# 5d.net
KiCad netlist of a schematic drawn in EAGLE
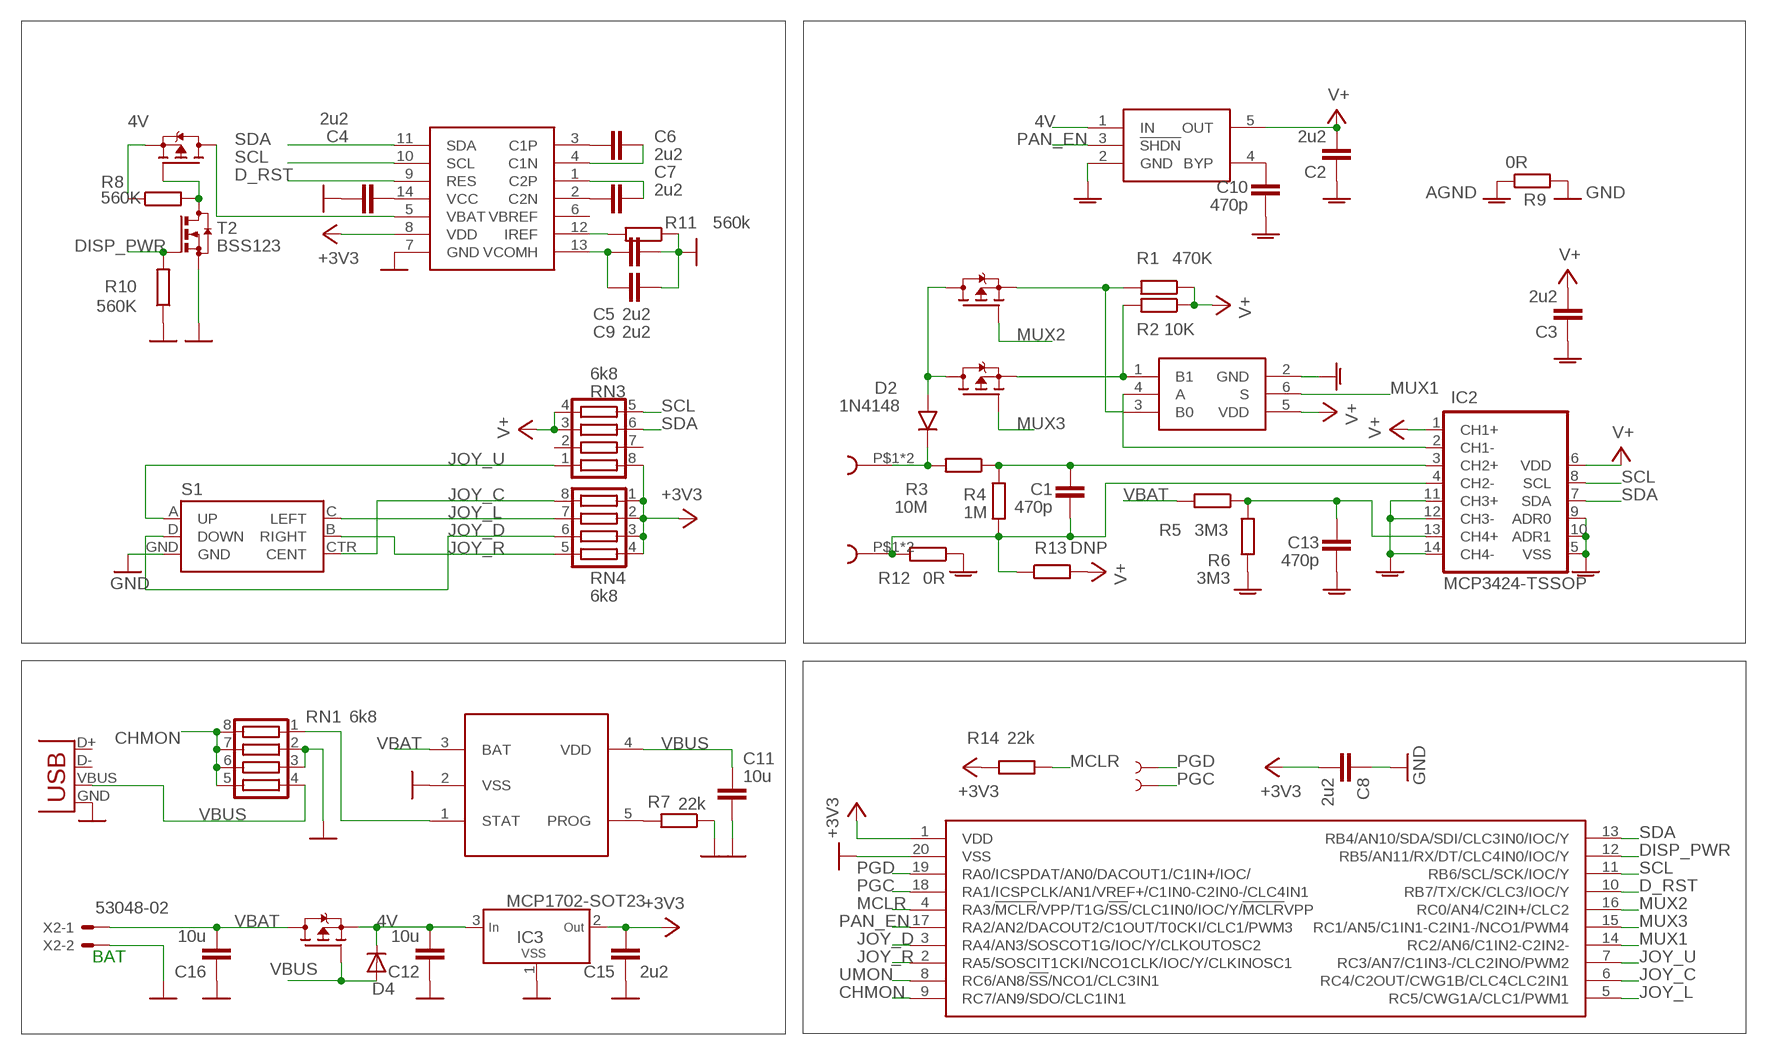
[diagram p0: schematic, sheet 1]

(export (version "E")
  (design (tool "Eeschema 10.0.6"))
  (components
    (comp (ref "C1")
      (value "470p")
      (footprint "eagle-import:0603")
      (libsource (lib "eagle-import") (part "C_0603"))
    )
    (comp (ref "C2")
      (value "2u2")
      (footprint "eagle-import:0603")
      (libsource (lib "eagle-import") (part "C_0603"))
    )
    (comp (ref "C3")
      (value "2u2")
      (footprint "eagle-import:0603")
      (libsource (lib "eagle-import") (part "C_0603"))
    )
    (comp (ref "C4")
      (value "2u2")
      (footprint "eagle-import:0603")
      (libsource (lib "eagle-import") (part "C_0603"))
    )
    (comp (ref "C5")
      (value "2u2")
      (footprint "eagle-import:0603")
      (libsource (lib "eagle-import") (part "C_0603"))
    )
    (comp (ref "C6")
      (value "2u2")
      (footprint "eagle-import:0603")
      (libsource (lib "eagle-import") (part "C_0603"))
    )
    (comp (ref "C7")
      (value "2u2")
      (footprint "eagle-import:0603")
      (libsource (lib "eagle-import") (part "C_0603"))
    )
    (comp (ref "C8")
      (value "2u2")
      (footprint "eagle-import:0603")
      (libsource (lib "eagle-import") (part "C_0603"))
    )
    (comp (ref "C9")
      (value "2u2")
      (footprint "eagle-import:0603")
      (libsource (lib "eagle-import") (part "C_0603"))
    )
    (comp (ref "C10")
      (value "470p")
      (footprint "eagle-import:0603")
      (libsource (lib "eagle-import") (part "C_0603"))
    )
    (comp (ref "C11")
      (value "10u")
      (footprint "eagle-import:R0805")
      (libsource (lib "eagle-import") (part "C_0806"))
    )
    (comp (ref "C12")
      (value "10u")
      (footprint "eagle-import:R0805")
      (libsource (lib "eagle-import") (part "C_0806"))
    )
    (comp (ref "C13")
      (value "470p")
      (footprint "eagle-import:0603")
      (libsource (lib "eagle-import") (part "C_0603"))
    )
    (comp (ref "C15")
      (value "2u2")
      (footprint "eagle-import:0603")
      (libsource (lib "eagle-import") (part "C_0603"))
    )
    (comp (ref "C16")
      (value "10u")
      (footprint "eagle-import:R0805")
      (libsource (lib "eagle-import") (part "C_0806"))
    )
    (comp (ref "D1")
      (value "DISP_OLED_049B")
      (footprint "eagle-import:DISP_OLED_049_B")
      (libsource (lib "eagle-import") (part "DISP_OLED_049B"))
    )
    (comp (ref "D2")
      (value "1N4148")
      (footprint "eagle-import:SOD-80")
      (libsource (lib "eagle-import") (part "1N4148SOD"))
    )
    (comp (ref "D4")
      (value "DIODE-SOD123")
      (footprint "eagle-import:SOD123")
      (libsource (lib "eagle-import") (part "DIODE-SOD123"))
    )
    (comp (ref "IC2")
      (value "MCP3424-TSSOP")
      (footprint "eagle-import:TSSOP14")
      (libsource (lib "eagle-import") (part "MCP3424-TSSOP"))
    )
    (comp (ref "IC3")
      (value "MCP1702-SOT23")
      (footprint "eagle-import:SOT23")
      (libsource (lib "eagle-import") (part "MCP1702-SOT23"))
    )
    (comp (ref "IC5")
      (value "NC7SB3157")
      (footprint "eagle-import:SC70-6")
      (libsource (lib "eagle-import") (part "NC7SB3157"))
    )
    (comp (ref "R1")
      (value "470K")
      (footprint "eagle-import:R0805")
      (libsource (lib "eagle-import") (part "R_0805"))
    )
    (comp (ref "R2")
      (value "10K")
      (footprint "eagle-import:R0805")
      (libsource (lib "eagle-import") (part "R_0805"))
    )
    (comp (ref "R3")
      (value "10M")
      (footprint "eagle-import:R0805")
      (libsource (lib "eagle-import") (part "R_0805"))
    )
    (comp (ref "R4")
      (value "1M")
      (footprint "eagle-import:R0805")
      (libsource (lib "eagle-import") (part "R_0805"))
    )
    (comp (ref "R5")
      (value "3M3")
      (footprint "eagle-import:0603")
      (libsource (lib "eagle-import") (part "R_0603"))
    )
    (comp (ref "R6")
      (value "3M3")
      (footprint "eagle-import:0603")
      (libsource (lib "eagle-import") (part "R_0603"))
    )
    (comp (ref "R7")
      (value "22k")
      (footprint "eagle-import:0603")
      (libsource (lib "eagle-import") (part "R_0603"))
    )
    (comp (ref "R8")
      (value "560K")
      (footprint "eagle-import:0603")
      (libsource (lib "eagle-import") (part "R_0603"))
    )
    (comp (ref "R9")
      (value "0R")
      (footprint "eagle-import:0603")
      (libsource (lib "eagle-import") (part "R_0603"))
    )
    (comp (ref "R10")
      (value "560K")
      (footprint "eagle-import:0603")
      (libsource (lib "eagle-import") (part "R_0603"))
    )
    (comp (ref "R11")
      (value "560k")
      (footprint "eagle-import:0603")
      (libsource (lib "eagle-import") (part "R_0603"))
    )
    (comp (ref "R12")
      (value "0R")
      (footprint "eagle-import:0603")
      (libsource (lib "eagle-import") (part "R_0603"))
    )
    (comp (ref "R13")
      (value "DNP")
      (footprint "eagle-import:0603")
      (libsource (lib "eagle-import") (part "R_0603"))
    )
    (comp (ref "R14")
      (value "22k")
      (footprint "eagle-import:0603")
      (libsource (lib "eagle-import") (part "R_0603"))
    )
    (comp (ref "RN1")
      (value "6k8")
      (footprint "eagle-import:CTS742C083")
      (libsource (lib "eagle-import") (part "CTS742C083"))
    )
    (comp (ref "RN3")
      (value "6k8")
      (footprint "eagle-import:CTS742C083")
      (libsource (lib "eagle-import") (part "CTS742C083"))
    )
    (comp (ref "RN4")
      (value "6k8")
      (footprint "eagle-import:CTS742C083")
      (libsource (lib "eagle-import") (part "CTS742C083"))
    )
    (comp (ref "S1")
      (value "JOYSTICK_MINI")
      (footprint "eagle-import:JOYSTICK_MINI")
      (libsource (lib "eagle-import") (part "JOYSTICK_MINI"))
    )
    (comp (ref "T1")
      (value "BSS84")
      (footprint "eagle-import:SOT23-3")
      (libsource (lib "eagle-import") (part "BSS84"))
    )
    (comp (ref "T2")
      (value "BSS123")
      (footprint "eagle-import:SOT23")
      (libsource (lib "eagle-import") (part "BSS123"))
    )
    (comp (ref "T3")
      (value "BSS84")
      (footprint "eagle-import:SOT23-3")
      (libsource (lib "eagle-import") (part "BSS84"))
    )
    (comp (ref "T4")
      (value "BSS84")
      (footprint "eagle-import:SOT23-3")
      (libsource (lib "eagle-import") (part "BSS84"))
    )
    (comp (ref "T5")
      (value "BSS84")
      (footprint "eagle-import:SOT23-3")
      (libsource (lib "eagle-import") (part "BSS84"))
    )
    (comp (ref "TP1")
      (value "TEST-POINT3X5")
      (footprint "eagle-import:PAD.03X.05")
      (libsource (lib "eagle-import") (part "TEST-POINT3X5"))
    )
    (comp (ref "TP2")
      (value "TEST-POINT3X5")
      (footprint "eagle-import:PAD.03X.05")
      (libsource (lib "eagle-import") (part "TEST-POINT3X5"))
    )
    (comp (ref "U$1")
      (value "BANPLUG_2")
      (footprint "eagle-import:BANPLUG_2")
      (libsource (lib "eagle-import") (part "BANPLUG_2"))
    )
    (comp (ref "U$2")
      (value "BANPLUG_2")
      (footprint "eagle-import:BANPLUG_2")
      (libsource (lib "eagle-import") (part "BANPLUG_2"))
    )
    (comp (ref "U$3")
      (value "TC1015")
      (footprint "eagle-import:SOT23-5")
      (libsource (lib "eagle-import") (part "TC1015"))
    )
    (comp (ref "U$4")
      (value "MCP73831")
      (footprint "eagle-import:SOT23-5")
      (libsource (lib "eagle-import") (part "MCP73831"))
    )
    (comp (ref "U$6")
      (value "PIC16F1508SSOP20")
      (footprint "eagle-import:SSOP20")
      (libsource (lib "eagle-import") (part "PIC16F1508SSOP20"))
    )
    (comp (ref "X1")
      (value "USB-MICROB")
      (footprint "eagle-import:USB-MICROB")
      (libsource (lib "eagle-import") (part "USB-MICROB"))
    )
    (comp (ref "X2")
      (value "53048-02")
      (footprint "eagle-import:53048-02")
      (libsource (lib "eagle-import") (part "53?-02048"))
    )
  )
  (nets
    (net (code "1") (name "+3V3") (class "Default")
      (node (ref "C15") (pin "2") (pinfunction "2_2") (pintype "passive"))
      (node (ref "C8") (pin "2") (pinfunction "2_2") (pintype "passive"))
      (node (ref "D1") (pin "8") (pinfunction "VDD_8") (pintype "bidirectional"))
      (node (ref "IC3") (pin "2") (pinfunction "OUT_2") (pintype "output"))
      (node (ref "R14") (pin "2") (pinfunction "2_2") (pintype "passive"))
      (node (ref "RN3") (pin "8") (pinfunction "8_8") (pintype "passive"))
      (node (ref "RN4") (pin "1") (pinfunction "1_1") (pintype "passive"))
      (node (ref "RN4") (pin "2") (pinfunction "2_2") (pintype "passive"))
      (node (ref "RN4") (pin "3") (pinfunction "3_3") (pintype "passive"))
      (node (ref "RN4") (pin "4") (pinfunction "4_4") (pintype "passive"))
      (node (ref "U$6") (pin "1") (pinfunction "VDD_1") (pintype "bidirectional"))
    )
    (net (code "2") (name "/4V") (class "Default")
      (node (ref "C12") (pin "2") (pinfunction "2_2") (pintype "passive"))
      (node (ref "D4") (pin "C") (pinfunction "C_C") (pintype "passive"))
      (node (ref "IC3") (pin "3") (pinfunction "IN_3") (pintype "input"))
      (node (ref "R8") (pin "1") (pinfunction "1_1") (pintype "passive"))
      (node (ref "T1") (pin "2") (pinfunction "S_2") (pintype "passive"))
      (node (ref "T3") (pin "2") (pinfunction "S_2") (pintype "passive"))
      (node (ref "U$3") (pin "1") (pinfunction "IN_1") (pintype "bidirectional"))
    )
    (net (code "3") (name "/CHMON") (class "Default")
      (node (ref "RN1") (pin "5") (pinfunction "5_5") (pintype "passive"))
      (node (ref "RN1") (pin "6") (pinfunction "6_6") (pintype "passive"))
      (node (ref "RN1") (pin "7") (pinfunction "7_7") (pintype "passive"))
      (node (ref "RN1") (pin "8") (pinfunction "8_8") (pintype "passive"))
      (node (ref "U$6") (pin "9") (pinfunction "RC7/AN9/SDO/CLC1IN1_9") (pintype "bidirectional"))
    )
    (net (code "4") (name "/DISP_PWR") (class "Default")
      (node (ref "R10") (pin "2") (pinfunction "2_2") (pintype "passive"))
      (node (ref "T2") (pin "1") (pinfunction "G_1") (pintype "passive"))
      (node (ref "U$6") (pin "12") (pinfunction "RB5/AN11/RX/DT/CLC4IN0/IOC/Y_12") (pintype "bidirectional"))
    )
    (net (code "5") (name "/D_RST") (class "Default")
      (node (ref "D1") (pin "9") (pinfunction "RES_9") (pintype "bidirectional"))
      (node (ref "U$6") (pin "10") (pinfunction "RB7/TX/CK/CLC3/IOC/Y_10") (pintype "bidirectional"))
    )
    (net (code "6") (name "/JOY_C") (class "Default")
      (node (ref "RN4") (pin "8") (pinfunction "8_8") (pintype "passive"))
      (node (ref "S1") (pin "CTR") (pinfunction "CENT_CTR") (pintype "bidirectional"))
      (node (ref "U$6") (pin "6") (pinfunction "RC4/C2OUT/CWG1B/CLC4CLC2IN1_6") (pintype "bidirectional"))
    )
    (net (code "7") (name "/JOY_D") (class "Default")
      (node (ref "RN4") (pin "6") (pinfunction "6_6") (pintype "passive"))
      (node (ref "S1") (pin "D") (pinfunction "DOWN_D") (pintype "bidirectional"))
      (node (ref "U$6") (pin "3") (pinfunction "RA4/AN3/SOSCOT1G/IOC/Y/CLKOUTOSC2_3") (pintype "bidirectional"))
    )
    (net (code "8") (name "/JOY_L") (class "Default")
      (node (ref "RN4") (pin "7") (pinfunction "7_7") (pintype "passive"))
      (node (ref "S1") (pin "C") (pinfunction "LEFT_C") (pintype "bidirectional"))
      (node (ref "U$6") (pin "5") (pinfunction "RC5/CWG1A/CLC1/PWM1_5") (pintype "bidirectional"))
    )
    (net (code "9") (name "/JOY_R") (class "Default")
      (node (ref "RN4") (pin "5") (pinfunction "5_5") (pintype "passive"))
      (node (ref "S1") (pin "B") (pinfunction "RIGHT_B") (pintype "bidirectional"))
      (node (ref "U$6") (pin "2") (pinfunction "RA5/SOSCIT1CKI/NCO1CLK/IOC/Y/CLKINOSC1_2") (pintype "bidirectional"))
    )
    (net (code "10") (name "/JOY_U") (class "Default")
      (node (ref "RN3") (pin "1") (pinfunction "1_1") (pintype "passive"))
      (node (ref "S1") (pin "A") (pinfunction "UP_A") (pintype "bidirectional"))
      (node (ref "U$6") (pin "7") (pinfunction "RC3/AN7/C1IN3-/CLC2INO/PWM2_7") (pintype "bidirectional"))
    )
    (net (code "11") (name "/MCLR") (class "Default")
      (node (ref "R14") (pin "1") (pinfunction "1_1") (pintype "passive"))
      (node (ref "U$6") (pin "4") (pinfunction "RA3/~{MCLR}/VPP/T1G/~{SS}/CLC1IN0/IOC/Y/~{MCLR}VPP_4") (pintype "bidirectional"))
    )
    (net (code "12") (name "/MUX1") (class "Default")
      (node (ref "IC5") (pin "6") (pinfunction "S_6") (pintype "bidirectional"))
      (node (ref "U$6") (pin "14") (pinfunction "RC2/AN6/C1IN2-C2IN2-_14") (pintype "bidirectional"))
    )
    (net (code "13") (name "/MUX2") (class "Default")
      (node (ref "T4") (pin "1") (pinfunction "G_1") (pintype "passive"))
      (node (ref "U$6") (pin "16") (pinfunction "RC0/AN4/C2IN+/CLC2_16") (pintype "bidirectional"))
    )
    (net (code "14") (name "/MUX3") (class "Default")
      (node (ref "T5") (pin "1") (pinfunction "G_1") (pintype "passive"))
      (node (ref "U$6") (pin "15") (pinfunction "RC1/AN5/C1IN1-C2IN1-/NCO1/PWM4_15") (pintype "bidirectional"))
    )
    (net (code "15") (name "/PAN_EN") (class "Default")
      (node (ref "U$3") (pin "3") (pinfunction "~{SHDN}_3") (pintype "bidirectional"))
      (node (ref "U$6") (pin "17") (pinfunction "RA2/AN2/DACOUT2/C1OUT/T0CKI/CLC1/PWM3_17") (pintype "bidirectional"))
    )
    (net (code "16") (name "/PGC") (class "Default")
      (node (ref "TP2") (pin "P$1") (pinfunction "1_P$1") (pintype "bidirectional"))
      (node (ref "U$6") (pin "18") (pinfunction "RA1/ICSPCLK/AN1/VREF+/C1IN0-C2IN0-/CLC4IN1_18") (pintype "bidirectional"))
    )
    (net (code "17") (name "/PGD") (class "Default")
      (node (ref "TP1") (pin "P$1") (pinfunction "1_P$1") (pintype "bidirectional"))
      (node (ref "U$6") (pin "19") (pinfunction "RA0/ICSPDAT/AN0/DACOUT1/C1IN+/IOC/_19") (pintype "bidirectional"))
    )
    (net (code "18") (name "/SCL") (class "Default")
      (node (ref "D1") (pin "10") (pinfunction "SCL_10") (pintype "bidirectional"))
      (node (ref "IC2") (pin "8") (pinfunction "SCL_8") (pintype "bidirectional"))
      (node (ref "RN3") (pin "5") (pinfunction "5_5") (pintype "passive"))
      (node (ref "U$6") (pin "11") (pinfunction "RB6/SCL/SCK/IOC/Y_11") (pintype "bidirectional"))
    )
    (net (code "19") (name "/SDA") (class "Default")
      (node (ref "D1") (pin "11") (pinfunction "SDA_11") (pintype "bidirectional"))
      (node (ref "IC2") (pin "7") (pinfunction "SDA_7") (pintype "bidirectional"))
      (node (ref "RN3") (pin "6") (pinfunction "6_6") (pintype "passive"))
      (node (ref "U$6") (pin "13") (pinfunction "RB4/AN10/SDA/SDI/CLC3IN0/IOC/Y_13") (pintype "bidirectional"))
    )
    (net (code "20") (name "/UMON") (class "Default")
      (node (ref "U$6") (pin "8") (pinfunction "RC6/AN8/~{SS}/NCO1/CLC3IN1_8") (pintype "bidirectional"))
    )
    (net (code "21") (name "/VBAT") (class "Default")
      (node (ref "C16") (pin "2") (pinfunction "2_2") (pintype "passive"))
      (node (ref "R5") (pin "2") (pinfunction "2_2") (pintype "passive"))
      (node (ref "T1") (pin "3") (pinfunction "D_3") (pintype "passive"))
      (node (ref "U$4") (pin "3") (pinfunction "BAT_3") (pintype "bidirectional"))
      (node (ref "X2") (pin "1") (pinfunction "S_1") (pintype "passive"))
    )
    (net (code "22") (name "/VBUS") (class "Default")
      (node (ref "C11") (pin "1") (pinfunction "1_1") (pintype "passive"))
      (node (ref "D4") (pin "A") (pinfunction "A_A") (pintype "passive"))
      (node (ref "RN1") (pin "4") (pinfunction "4_4") (pintype "passive"))
      (node (ref "T1") (pin "1") (pinfunction "G_1") (pintype "passive"))
      (node (ref "U$4") (pin "4") (pinfunction "VDD_4") (pintype "bidirectional"))
      (node (ref "X1") (pin "VBUS") (pinfunction "VBUS_VBUS") (pintype "bidirectional"))
    )
    (net (code "23") (name "AGND") (class "Default")
      (node (ref "C10") (pin "1") (pinfunction "1_1") (pintype "passive"))
      (node (ref "C13") (pin "1") (pinfunction "1_1") (pintype "passive"))
      (node (ref "C2") (pin "1") (pinfunction "1_1") (pintype "passive"))
      (node (ref "C3") (pin "1") (pinfunction "1_1") (pintype "passive"))
      (node (ref "IC2") (pin "10") (pinfunction "ADR1_10") (pintype "bidirectional"))
      (node (ref "IC2") (pin "11") (pinfunction "CH3+_11") (pintype "bidirectional"))
      (node (ref "IC2") (pin "12") (pinfunction "CH3-_12") (pintype "bidirectional"))
      (node (ref "IC2") (pin "14") (pinfunction "CH4-_14") (pintype "bidirectional"))
      (node (ref "IC2") (pin "5") (pinfunction "VSS_5") (pintype "power_in"))
      (node (ref "IC2") (pin "9") (pinfunction "ADR0_9") (pintype "bidirectional"))
      (node (ref "IC5") (pin "2") (pinfunction "GND_2") (pintype "bidirectional"))
      (node (ref "R12") (pin "1") (pinfunction "1_1") (pintype "passive"))
      (node (ref "R6") (pin "2") (pinfunction "2_2") (pintype "passive"))
      (node (ref "R9") (pin "1") (pinfunction "1_1") (pintype "passive"))
      (node (ref "U$3") (pin "2") (pinfunction "GND_2") (pintype "bidirectional"))
    )
    (net (code "24") (name "GND") (class "Default")
      (node (ref "C11") (pin "2") (pinfunction "2_2") (pintype "passive"))
      (node (ref "C12") (pin "1") (pinfunction "1_1") (pintype "passive"))
      (node (ref "C15") (pin "1") (pinfunction "1_1") (pintype "passive"))
      (node (ref "C16") (pin "1") (pinfunction "1_1") (pintype "passive"))
      (node (ref "C4") (pin "1") (pinfunction "1_1") (pintype "passive"))
      (node (ref "C5") (pin "2") (pinfunction "2_2") (pintype "passive"))
      (node (ref "C8") (pin "1") (pinfunction "1_1") (pintype "passive"))
      (node (ref "C9") (pin "2") (pinfunction "2_2") (pintype "passive"))
      (node (ref "D1") (pin "7") (pinfunction "GND_7") (pintype "bidirectional"))
      (node (ref "IC3") (pin "1") (pinfunction "VSS_1") (pintype "input"))
      (node (ref "R10") (pin "1") (pinfunction "1_1") (pintype "passive"))
      (node (ref "R11") (pin "1") (pinfunction "1_1") (pintype "passive"))
      (node (ref "R7") (pin "1") (pinfunction "1_1") (pintype "passive"))
      (node (ref "R9") (pin "2") (pinfunction "2_2") (pintype "passive"))
      (node (ref "RN1") (pin "2") (pinfunction "2_2") (pintype "passive"))
      (node (ref "RN1") (pin "3") (pinfunction "3_3") (pintype "passive"))
      (node (ref "S1") (pin "GND") (pinfunction "GND_GND") (pintype "bidirectional"))
      (node (ref "T2") (pin "2") (pinfunction "S_2") (pintype "passive"))
      (node (ref "U$4") (pin "2") (pinfunction "VSS_2") (pintype "bidirectional"))
      (node (ref "U$6") (pin "20") (pinfunction "VSS_20") (pintype "bidirectional"))
      (node (ref "X1") (pin "GND") (pinfunction "GND_GND") (pintype "bidirectional"))
      (node (ref "X2") (pin "2") (pinfunction "S_2") (pintype "passive"))
    )
    (net (code "25") (name "Net-(D1-C1N)") (class "Default")
      (node (ref "C6") (pin "2") (pinfunction "2_2") (pintype "passive"))
      (node (ref "D1") (pin "4") (pinfunction "C1N_4") (pintype "bidirectional"))
    )
    (net (code "26") (name "Net-(D1-C1P)") (class "Default")
      (node (ref "C6") (pin "1") (pinfunction "1_1") (pintype "passive"))
      (node (ref "D1") (pin "3") (pinfunction "C1P_3") (pintype "bidirectional"))
    )
    (net (code "27") (name "Net-(D1-C2N)") (class "Default")
      (node (ref "C7") (pin "1") (pinfunction "1_1") (pintype "passive"))
      (node (ref "D1") (pin "2") (pinfunction "C2N_2") (pintype "bidirectional"))
    )
    (net (code "28") (name "Net-(D1-C2P)") (class "Default")
      (node (ref "C7") (pin "2") (pinfunction "2_2") (pintype "passive"))
      (node (ref "D1") (pin "1") (pinfunction "C2P_1") (pintype "bidirectional"))
    )
    (net (code "29") (name "Net-(D1-IREF)") (class "Default")
      (node (ref "D1") (pin "12") (pinfunction "IREF_12") (pintype "bidirectional"))
      (node (ref "R11") (pin "2") (pinfunction "2_2") (pintype "passive"))
    )
    (net (code "30") (name "Net-(D1-VBAT)") (class "Default")
      (node (ref "D1") (pin "5") (pinfunction "VBAT_5") (pintype "bidirectional"))
      (node (ref "T3") (pin "3") (pinfunction "D_3") (pintype "passive"))
    )
    (net (code "31") (name "Net-(D1-VCC)") (class "Default")
      (node (ref "C4") (pin "2") (pinfunction "2_2") (pintype "passive"))
      (node (ref "D1") (pin "14") (pinfunction "VCC_14") (pintype "bidirectional"))
    )
    (net (code "32") (name "Net-(D1-VCOMH)") (class "Default")
      (node (ref "C5") (pin "1") (pinfunction "1_1") (pintype "passive"))
      (node (ref "C9") (pin "1") (pinfunction "1_1") (pintype "passive"))
      (node (ref "D1") (pin "13") (pinfunction "VCOMH_13") (pintype "bidirectional"))
    )
    (net (code "33") (name "Net-(D2-PadK)") (class "Default")
      (node (ref "D2") (pin "K") (pinfunction "K_K") (pintype "output"))
      (node (ref "R3") (pin "2") (pinfunction "2_2") (pintype "passive"))
      (node (ref "U$1") (pin "P$1") (pinfunction "P$1_P$1") (pintype "bidirectional"))
      (node (ref "U$1") (pin "P$2") (pinfunction "P$1_P$2") (pintype "bidirectional"))
    )
    (net (code "34") (name "Net-(IC2-CH1-)") (class "Default")
      (node (ref "IC2") (pin "2") (pinfunction "CH1-_2") (pintype "bidirectional"))
      (node (ref "IC5") (pin "4") (pinfunction "A_4") (pintype "bidirectional"))
    )
    (net (code "35") (name "Net-(IC2-CH2+)") (class "Default")
      (node (ref "C1") (pin "2") (pinfunction "2_2") (pintype "passive"))
      (node (ref "IC2") (pin "3") (pinfunction "CH2+_3") (pintype "bidirectional"))
      (node (ref "R3") (pin "1") (pinfunction "1_1") (pintype "passive"))
      (node (ref "R4") (pin "1") (pinfunction "1_1") (pintype "passive"))
    )
    (net (code "36") (name "Net-(IC2-CH2-)") (class "Default")
      (node (ref "C1") (pin "1") (pinfunction "1_1") (pintype "passive"))
      (node (ref "IC2") (pin "4") (pinfunction "CH2-_4") (pintype "bidirectional"))
      (node (ref "R12") (pin "2") (pinfunction "2_2") (pintype "passive"))
      (node (ref "R13") (pin "1") (pinfunction "1_1") (pintype "passive"))
      (node (ref "R4") (pin "2") (pinfunction "2_2") (pintype "passive"))
      (node (ref "U$2") (pin "P$1") (pinfunction "P$1_P$1") (pintype "bidirectional"))
      (node (ref "U$2") (pin "P$2") (pinfunction "P$1_P$2") (pintype "bidirectional"))
    )
    (net (code "37") (name "Net-(IC2-CH4+)") (class "Default")
      (node (ref "C13") (pin "2") (pinfunction "2_2") (pintype "passive"))
      (node (ref "IC2") (pin "13") (pinfunction "CH4+_13") (pintype "bidirectional"))
      (node (ref "R5") (pin "1") (pinfunction "1_1") (pintype "passive"))
      (node (ref "R6") (pin "1") (pinfunction "1_1") (pintype "passive"))
    )
    (net (code "38") (name "Net-(IC5-B0)") (class "Default")
      (node (ref "IC5") (pin "3") (pinfunction "B0_3") (pintype "bidirectional"))
      (node (ref "R1") (pin "2") (pinfunction "2_2") (pintype "passive"))
      (node (ref "T4") (pin "2") (pinfunction "S_2") (pintype "passive"))
    )
    (net (code "39") (name "Net-(IC5-B1)") (class "Default")
      (node (ref "IC5") (pin "1") (pinfunction "B1_1") (pintype "bidirectional"))
      (node (ref "R2") (pin "2") (pinfunction "2_2") (pintype "passive"))
      (node (ref "T5") (pin "2") (pinfunction "S_2") (pintype "passive"))
    )
    (net (code "40") (name "Net-(T2-D)") (class "Default")
      (node (ref "R8") (pin "2") (pinfunction "2_2") (pintype "passive"))
      (node (ref "T2") (pin "3") (pinfunction "D_3") (pintype "passive"))
      (node (ref "T3") (pin "1") (pinfunction "G_1") (pintype "passive"))
    )
    (net (code "41") (name "Net-(T4-D)") (class "Default")
      (node (ref "D2") (pin "A") (pinfunction "A_A") (pintype "input"))
      (node (ref "T4") (pin "3") (pinfunction "D_3") (pintype "passive"))
      (node (ref "T5") (pin "3") (pinfunction "D_3") (pintype "passive"))
    )
    (net (code "42") (name "Net-(U$3-BYP)") (class "Default")
      (node (ref "C10") (pin "2") (pinfunction "2_2") (pintype "passive"))
      (node (ref "U$3") (pin "4") (pinfunction "BYP_4") (pintype "bidirectional"))
    )
    (net (code "43") (name "Net-(U$4-PROG)") (class "Default")
      (node (ref "R7") (pin "2") (pinfunction "2_2") (pintype "passive"))
      (node (ref "U$4") (pin "5") (pinfunction "PROG_5") (pintype "bidirectional"))
    )
    (net (code "44") (name "Net-(U$4-STAT)") (class "Default")
      (node (ref "RN1") (pin "1") (pinfunction "1_1") (pintype "passive"))
      (node (ref "U$4") (pin "1") (pinfunction "STAT_1") (pintype "bidirectional"))
    )
    (net (code "45") (name "V+") (class "Default")
      (node (ref "C2") (pin "2") (pinfunction "2_2") (pintype "passive"))
      (node (ref "C3") (pin "2") (pinfunction "2_2") (pintype "passive"))
      (node (ref "IC2") (pin "1") (pinfunction "CH1+_1") (pintype "bidirectional"))
      (node (ref "IC2") (pin "6") (pinfunction "VDD_6") (pintype "power_in"))
      (node (ref "IC5") (pin "5") (pinfunction "VDD_5") (pintype "bidirectional"))
      (node (ref "R1") (pin "1") (pinfunction "1_1") (pintype "passive"))
      (node (ref "R13") (pin "2") (pinfunction "2_2") (pintype "passive"))
      (node (ref "R2") (pin "1") (pinfunction "1_1") (pintype "passive"))
      (node (ref "RN3") (pin "3") (pinfunction "3_3") (pintype "passive"))
      (node (ref "RN3") (pin "4") (pinfunction "4_4") (pintype "passive"))
      (node (ref "U$3") (pin "5") (pinfunction "OUT_5") (pintype "bidirectional"))
    )
    (net (code "46") (name "unconnected-(D1-VBREF-Pad6)") (class "Default")
      (node (ref "D1") (pin "6") (pinfunction "VBREF_6") (pintype "bidirectional"))
    )
    (net (code "47") (name "unconnected-(RN3-Pad2)") (class "Default")
      (node (ref "RN3") (pin "2") (pinfunction "2_2") (pintype "passive"))
    )
    (net (code "48") (name "unconnected-(RN3-Pad7)") (class "Default")
      (node (ref "RN3") (pin "7") (pinfunction "7_7") (pintype "passive"))
    )
    (net (code "49") (name "unconnected-(X1-PadD+)") (class "Default")
      (node (ref "X1") (pin "D+") (pinfunction "D+_D+") (pintype "bidirectional"))
    )
    (net (code "50") (name "unconnected-(X1-PadD-)") (class "Default")
      (node (ref "X1") (pin "D-") (pinfunction "D-_D-") (pintype "bidirectional"))
    )
  )
)
